# RTC.net
KiCad netlist of a schematic drawn in EAGLE
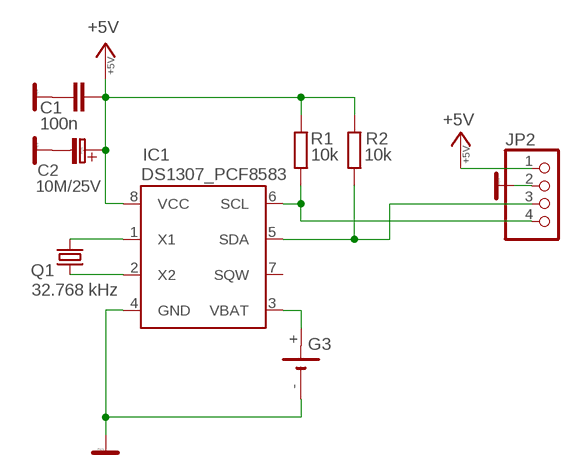
[diagram p0: schematic, sheet 1]

(export (version "E")
  (design (tool "Eeschema 10.0.6"))
  (components
    (comp (ref "C1")
      (value "100n")
      (footprint "eagle-import:KERAMICKY_RM5")
      (libsource (lib "eagle-import") (part "KERAMICKYRM5"))
    )
    (comp (ref "C2")
      (value "10M/25V")
      (footprint "eagle-import:C_EL_2")
      (libsource (lib "eagle-import") (part "10M/25V"))
    )
    (comp (ref "G3")
      (value "VL1220")
      (footprint "eagle-import:VL1220")
      (libsource (lib "eagle-import") (part "VL1220"))
    )
    (comp (ref "IC1")
      (value "DS1307_PCF8583")
      (footprint "eagle-import:DS1307_PCF8583_DIL08")
      (libsource (lib "eagle-import") (part "DS1307_PCF8583_DS1307"))
    )
    (comp (ref "JP2")
      (value "PINHD-1X4")
      (footprint "eagle-import:1X04")
      (libsource (lib "eagle-import") (part "PINHD-1X4"))
    )
    (comp (ref "Q1")
      (value "32.768 kHz")
      (footprint "eagle-import:GWX-26")
      (libsource (lib "eagle-import") (part "GWX-26"))
    )
    (comp (ref "R1")
      (value "10k")
      (footprint "eagle-import:0207_10")
      (libsource (lib "eagle-import") (part "R-EU_0207/10"))
    )
    (comp (ref "R2")
      (value "10k")
      (footprint "eagle-import:0207_10")
      (libsource (lib "eagle-import") (part "R-EU_0207/10"))
    )
  )
  (nets
    (net (code "1") (name "+5V") (class "Default")
      (node (ref "C1") (pin "P$1") (pinfunction "1_P$1") (pintype "passive"))
      (node (ref "C2") (pin "C+") (pinfunction "C_EL+_C+") (pintype "passive"))
      (node (ref "IC1") (pin "8") (pinfunction "VCC_8") (pintype "power_in"))
      (node (ref "JP2") (pin "1") (pinfunction "1_1") (pintype "passive"))
      (node (ref "R1") (pin "2") (pinfunction "2_2") (pintype "passive"))
      (node (ref "R2") (pin "2") (pinfunction "2_2") (pintype "passive"))
    )
    (net (code "2") (name "GND") (class "Default")
      (node (ref "C1") (pin "P$2") (pinfunction "2_P$2") (pintype "passive"))
      (node (ref "C2") (pin "C-") (pinfunction "C_EL-_C-") (pintype "passive"))
      (node (ref "G3") (pin "-") (pinfunction "-_-") (pintype "passive"))
      (node (ref "IC1") (pin "4") (pinfunction "GND_4") (pintype "power_in"))
      (node (ref "JP2") (pin "2") (pinfunction "2_2") (pintype "passive"))
    )
    (net (code "3") (name "Net-(IC1-SCL)") (class "Default")
      (node (ref "IC1") (pin "6") (pinfunction "SCL_6") (pintype "input"))
      (node (ref "JP2") (pin "4") (pinfunction "4_4") (pintype "passive"))
      (node (ref "R1") (pin "1") (pinfunction "1_1") (pintype "passive"))
    )
    (net (code "4") (name "Net-(IC1-SDA)") (class "Default")
      (node (ref "IC1") (pin "5") (pinfunction "SDA_5") (pintype "bidirectional"))
      (node (ref "JP2") (pin "3") (pinfunction "3_3") (pintype "passive"))
      (node (ref "R2") (pin "1") (pinfunction "1_1") (pintype "passive"))
    )
    (net (code "5") (name "Net-(IC1-VBAT)") (class "Default")
      (node (ref "G3") (pin "+") (pinfunction "+_+") (pintype "passive"))
      (node (ref "IC1") (pin "3") (pinfunction "VBAT_3") (pintype "passive"))
    )
    (net (code "6") (name "Net-(IC1-X1)") (class "Default")
      (node (ref "IC1") (pin "1") (pinfunction "X1_1") (pintype "input"))
      (node (ref "Q1") (pin "P$2") (pinfunction "2_P$2") (pintype "passive"))
    )
    (net (code "7") (name "Net-(IC1-X2)") (class "Default")
      (node (ref "IC1") (pin "2") (pinfunction "X2_2") (pintype "output"))
      (node (ref "Q1") (pin "P$1") (pinfunction "1_P$1") (pintype "passive"))
    )
    (net (code "8") (name "unconnected-(IC1-SQW-Pad7)") (class "Default")
      (node (ref "IC1") (pin "7") (pinfunction "SQW_7") (pintype "open_collector"))
    )
  )
)
